# Ext_connections.net
KiCad netlist of a schematic drawn in Altium Designer
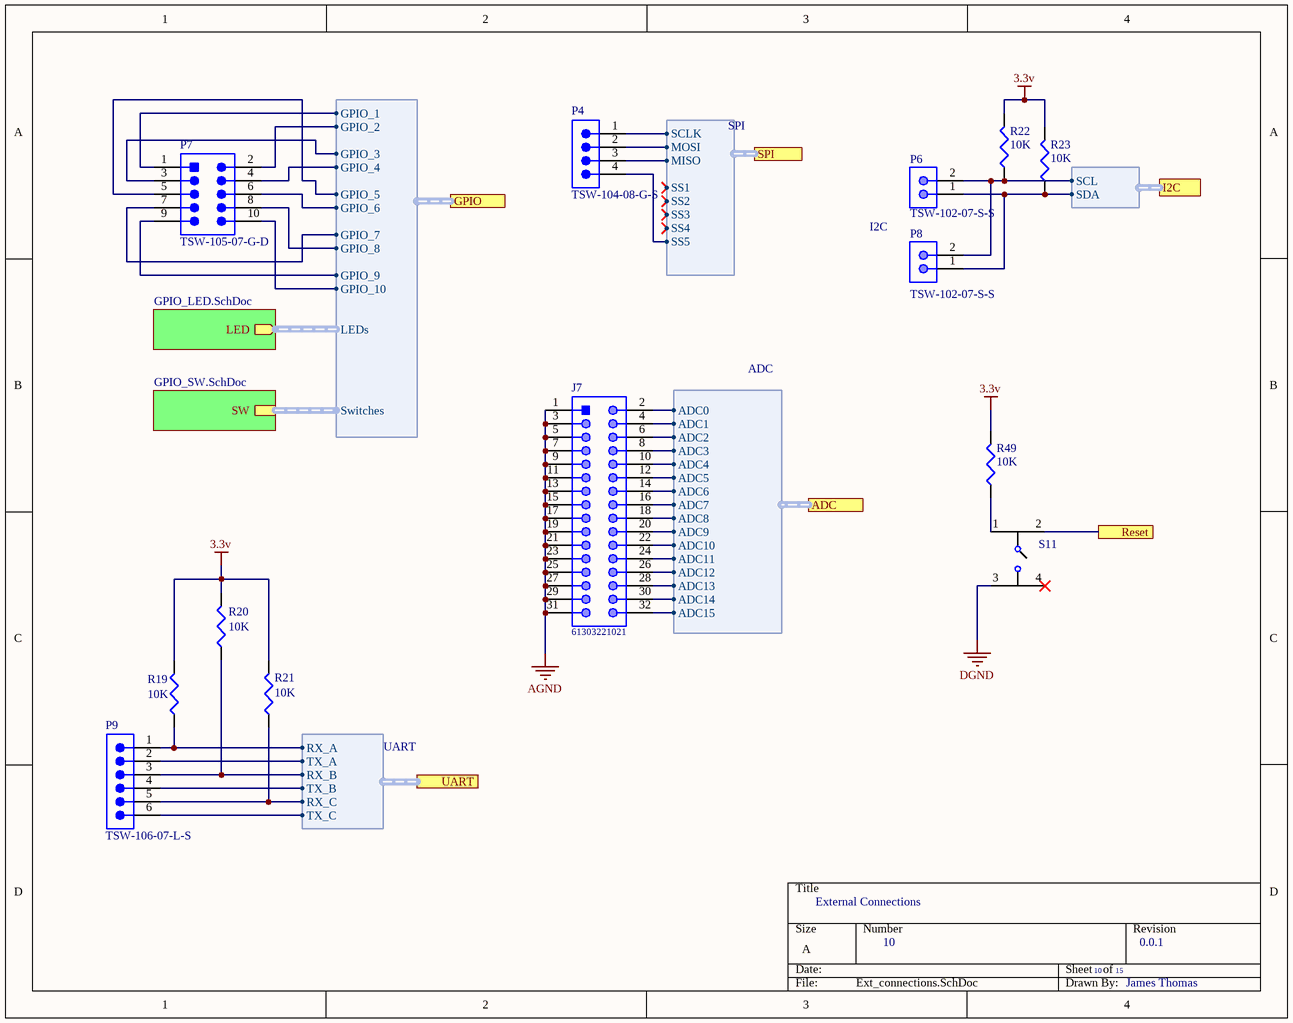
[diagram p0: Ext_connections.SchDoc]

(export (version "E")
  (design (tool "Eeschema 10.0.6"))
  (components
    (comp (ref "J7")
      (value "61303221021")
      (footprint "61303221021")
      (description "THT Angled Pin Header WR-PHD, Pitch 2.54 mm, Dual Row, 32 pins")
      (fields (field (name "MANUFACTURER") "Wurth Elektronik") (field (name "PUBLISHER") "WurthElektronik"))
      (libsource (lib "Altium Content Vault") (part "WE-CN-2P-M-R32"))
    )
    (comp (ref "P4")
      (value "TSW-104-08-G-S")
      (footprint "SMTC-TSW-104-08-X-S")
      (description "0.025\" SQ Post Header, Through-hole, Vertical, -55 to 125 degC, 2.54 mm Pitch, 4-Pin, Male, RoHS")
      (fields (field (name "MANUFACTURER") "Samtec"))
      (libsource (lib "Altium Content Vault") (part "SMTC-TSW-104-08-X-S"))
    )
    (comp (ref "P6")
      (value "TSW-102-07-S-S")
      (footprint "SMTC-TSW-102-07-S-S")
      (fields (field (name "MANUFACTURER") "Samtec"))
      (libsource (lib "Altium Content Vault") (part "CN-1P-M-R2"))
    )
    (comp (ref "P7")
      (value "TSW-105-07-G-D")
      (footprint "SMTC-TSW-105-07-G-D_V")
      (fields (field (name "MANUFACTURER") "Samtec-Inc."))
      (libsource (lib "Altium Content Vault") (part "CN-2P-M-R10"))
    )
    (comp (ref "P8")
      (value "TSW-102-07-S-S")
      (footprint "SMTC-TSW-102-07-S-S")
      (fields (field (name "MANUFACTURER") "Samtec"))
      (libsource (lib "Altium Content Vault") (part "CN-1P-M-R2"))
    )
    (comp (ref "P9")
      (value "TSW-106-07-L-S")
      (footprint "SMTC-TSW-106-07-X-S")
      (description "0.025\" SQ Post Header, Through-hole, Vertical, -55 to 125 degC, 2.54 mm Pitch, 6-Pin, Male, RoHS")
      (fields (field (name "MANUFACTURER") "Samtec"))
      (libsource (lib "Altium Content Vault") (part "SMTC-TSW-106-X-X-S-X"))
    )
    (comp (ref "R19")
      (value "10K")
      (footprint "J1-0603")
      (description "Resistor")
      (fields (field (name "Comment") "Res3") (field (name "PUBLISHER") "Altium Limited"))
      (libsource (lib "Miscellaneous Devices") (part "Res3"))
    )
    (comp (ref "R20")
      (value "10K")
      (footprint "J1-0603")
      (description "Resistor")
      (fields (field (name "Comment") "Res3") (field (name "PUBLISHER") "Altium Limited"))
      (libsource (lib "Miscellaneous Devices") (part "Res3"))
    )
    (comp (ref "R21")
      (value "10K")
      (footprint "J1-0603")
      (description "Resistor")
      (fields (field (name "Comment") "Res3") (field (name "PUBLISHER") "Altium Limited"))
      (libsource (lib "Miscellaneous Devices") (part "Res3"))
    )
    (comp (ref "R22")
      (value "10K")
      (footprint "J1-0603")
      (description "Resistor")
      (fields (field (name "Comment") "Res3") (field (name "PUBLISHER") "Altium Limited"))
      (libsource (lib "Miscellaneous Devices") (part "Res3"))
    )
    (comp (ref "R23")
      (value "10K")
      (footprint "J1-0603")
      (description "Resistor")
      (fields (field (name "Comment") "Res3") (field (name "PUBLISHER") "Altium Limited"))
      (libsource (lib "Miscellaneous Devices") (part "Res3"))
    )
    (comp (ref "R49")
      (value "10K")
      (footprint "J1-0603")
      (description "Resistor")
      (fields (field (name "Comment") "Res3") (field (name "PUBLISHER") "Altium Limited"))
      (libsource (lib "Miscellaneous Devices") (part "Res3"))
    )
    (comp (ref "S11")
      (value "430181038816")
      (footprint "*430181038816")
      (description "Tactile Switch SPST-NO Top Actuated Surface Mount")
      (fields (field (name "MF") "Wurth Electronics"))
      (libsource (lib "Components") (part "430181038816"))
    )
  )
  (nets
    (net (code "6") (name "/ADC0") (class "Default")
      (node (ref "J7") (pin "2") (pinfunction "2_2") (pintype "passive"))
    )
    (net (code "7") (name "/ADC1") (class "Default")
      (node (ref "J7") (pin "4") (pinfunction "4_4") (pintype "passive"))
    )
    (net (code "8") (name "/ADC2") (class "Default")
      (node (ref "J7") (pin "6") (pinfunction "6_6") (pintype "passive"))
    )
    (net (code "9") (name "/ADC3") (class "Default")
      (node (ref "J7") (pin "8") (pinfunction "8_8") (pintype "passive"))
    )
    (net (code "10") (name "/ADC4") (class "Default")
      (node (ref "J7") (pin "10") (pinfunction "10_10") (pintype "passive"))
    )
    (net (code "11") (name "/ADC5") (class "Default")
      (node (ref "J7") (pin "12") (pinfunction "12_12") (pintype "passive"))
    )
    (net (code "12") (name "/ADC6") (class "Default")
      (node (ref "J7") (pin "14") (pinfunction "14_14") (pintype "passive"))
    )
    (net (code "13") (name "/ADC7") (class "Default")
      (node (ref "J7") (pin "16") (pinfunction "16_16") (pintype "passive"))
    )
    (net (code "14") (name "/ADC8") (class "Default")
      (node (ref "J7") (pin "18") (pinfunction "18_18") (pintype "passive"))
    )
    (net (code "15") (name "/ADC9") (class "Default")
      (node (ref "J7") (pin "20") (pinfunction "20_20") (pintype "passive"))
    )
    (net (code "16") (name "/ADC10") (class "Default")
      (node (ref "J7") (pin "22") (pinfunction "22_22") (pintype "passive"))
    )
    (net (code "17") (name "/ADC11") (class "Default")
      (node (ref "J7") (pin "24") (pinfunction "24_24") (pintype "passive"))
    )
    (net (code "18") (name "/ADC12") (class "Default")
      (node (ref "J7") (pin "26") (pinfunction "26_26") (pintype "passive"))
    )
    (net (code "19") (name "/ADC13") (class "Default")
      (node (ref "J7") (pin "28") (pinfunction "28_28") (pintype "passive"))
    )
    (net (code "20") (name "/ADC14") (class "Default")
      (node (ref "J7") (pin "30") (pinfunction "30_30") (pintype "passive"))
    )
    (net (code "21") (name "/ADC15") (class "Default")
      (node (ref "J7") (pin "32") (pinfunction "32_32") (pintype "passive"))
    )
    (net (code "22") (name "/GPIO_1") (class "Default")
      (node (ref "P7") (pin "1") (pinfunction "1_1") (pintype "passive"))
    )
    (net (code "23") (name "/GPIO_2") (class "Default")
      (node (ref "P7") (pin "2") (pinfunction "2_2") (pintype "passive"))
    )
    (net (code "24") (name "/GPIO_3") (class "Default")
      (node (ref "P7") (pin "3") (pinfunction "3_3") (pintype "passive"))
    )
    (net (code "25") (name "/GPIO_4") (class "Default")
      (node (ref "P7") (pin "4") (pinfunction "4_4") (pintype "passive"))
    )
    (net (code "26") (name "/GPIO_5") (class "Default")
      (node (ref "P7") (pin "5") (pinfunction "5_5") (pintype "passive"))
    )
    (net (code "27") (name "/GPIO_6") (class "Default")
      (node (ref "P7") (pin "6") (pinfunction "6_6") (pintype "passive"))
    )
    (net (code "28") (name "/GPIO_7") (class "Default")
      (node (ref "P7") (pin "7") (pinfunction "7_7") (pintype "passive"))
    )
    (net (code "29") (name "/GPIO_8") (class "Default")
      (node (ref "P7") (pin "8") (pinfunction "8_8") (pintype "passive"))
    )
    (net (code "30") (name "/GPIO_9") (class "Default")
      (node (ref "P7") (pin "9") (pinfunction "9_9") (pintype "passive"))
    )
    (net (code "31") (name "/GPIO_10") (class "Default")
      (node (ref "P7") (pin "10") (pinfunction "10_10") (pintype "passive"))
    )
    (net (code "33") (name "/MISO") (class "Default")
      (node (ref "P4") (pin "3") (pinfunction "3_3") (pintype "passive"))
    )
    (net (code "34") (name "/MOSI") (class "Default")
      (node (ref "P4") (pin "2") (pinfunction "2_2") (pintype "passive"))
    )
    (net (code "35") (name "/RX_A") (class "Default")
      (node (ref "P9") (pin "1") (pinfunction "1_1") (pintype "passive"))
      (node (ref "R19") (pin "1") (pinfunction "1_1") (pintype "passive"))
    )
    (net (code "36") (name "/RX_B") (class "Default")
      (node (ref "P9") (pin "3") (pinfunction "3_3") (pintype "passive"))
      (node (ref "R20") (pin "1") (pinfunction "1_1") (pintype "passive"))
    )
    (net (code "37") (name "/RX_C") (class "Default")
      (node (ref "P9") (pin "5") (pinfunction "5_5") (pintype "passive"))
      (node (ref "R21") (pin "1") (pinfunction "1_1") (pintype "passive"))
    )
    (net (code "38") (name "/Reset") (class "Default")
      (node (ref "S11") (pin "2") (pinfunction "3_2") (pintype "passive"))
    )
    (net (code "39") (name "/SCL") (class "Default")
      (node (ref "P6") (pin "2") (pinfunction "2_2") (pintype "passive"))
      (node (ref "P8") (pin "2") (pinfunction "2_2") (pintype "passive"))
      (node (ref "R22") (pin "1") (pinfunction "1_1") (pintype "passive"))
    )
    (net (code "40") (name "/SCLK") (class "Default")
      (node (ref "P4") (pin "1") (pinfunction "1_1") (pintype "passive"))
    )
    (net (code "41") (name "/SDA") (class "Default")
      (node (ref "P6") (pin "1") (pinfunction "1_1") (pintype "passive"))
      (node (ref "P8") (pin "1") (pinfunction "1_1") (pintype "passive"))
      (node (ref "R23") (pin "1") (pinfunction "1_1") (pintype "passive"))
    )
    (net (code "42") (name "/SS5") (class "Default")
      (node (ref "P4") (pin "4") (pinfunction "4_4") (pintype "passive"))
    )
    (net (code "44") (name "/TX_A") (class "Default")
      (node (ref "P9") (pin "2") (pinfunction "2_2") (pintype "passive"))
    )
    (net (code "45") (name "/TX_B") (class "Default")
      (node (ref "P9") (pin "4") (pinfunction "4_4") (pintype "passive"))
    )
    (net (code "46") (name "/TX_C") (class "Default")
      (node (ref "P9") (pin "6") (pinfunction "6_6") (pintype "passive"))
    )
    (net (code "52") (name "3.3v") (class "Default")
      (node (ref "R19") (pin "2") (pinfunction "2_2") (pintype "passive"))
      (node (ref "R20") (pin "2") (pinfunction "2_2") (pintype "passive"))
      (node (ref "R21") (pin "2") (pinfunction "2_2") (pintype "passive"))
      (node (ref "R22") (pin "2") (pinfunction "2_2") (pintype "passive"))
      (node (ref "R23") (pin "2") (pinfunction "2_2") (pintype "passive"))
      (node (ref "R49") (pin "2") (pinfunction "2_2") (pintype "passive"))
    )
    (net (code "53") (name "AGND") (class "Default")
      (node (ref "J7") (pin "1") (pinfunction "1_1") (pintype "passive"))
      (node (ref "J7") (pin "11") (pinfunction "11_11") (pintype "passive"))
      (node (ref "J7") (pin "13") (pinfunction "13_13") (pintype "passive"))
      (node (ref "J7") (pin "15") (pinfunction "15_15") (pintype "passive"))
      (node (ref "J7") (pin "17") (pinfunction "17_17") (pintype "passive"))
      (node (ref "J7") (pin "19") (pinfunction "19_19") (pintype "passive"))
      (node (ref "J7") (pin "21") (pinfunction "21_21") (pintype "passive"))
      (node (ref "J7") (pin "23") (pinfunction "23_23") (pintype "passive"))
      (node (ref "J7") (pin "25") (pinfunction "25_25") (pintype "passive"))
      (node (ref "J7") (pin "27") (pinfunction "27_27") (pintype "passive"))
      (node (ref "J7") (pin "29") (pinfunction "29_29") (pintype "passive"))
      (node (ref "J7") (pin "3") (pinfunction "3_3") (pintype "passive"))
      (node (ref "J7") (pin "31") (pinfunction "31_31") (pintype "passive"))
      (node (ref "J7") (pin "5") (pinfunction "5_5") (pintype "passive"))
      (node (ref "J7") (pin "7") (pinfunction "7_7") (pintype "passive"))
      (node (ref "J7") (pin "9") (pinfunction "9_9") (pintype "passive"))
    )
    (net (code "54") (name "DGND") (class "Default")
      (node (ref "S11") (pin "3") (pinfunction "2_3") (pintype "passive"))
    )
    (net (code "55") (name "Net-(R49-Pad1)") (class "Default")
      (node (ref "R49") (pin "1") (pinfunction "1_1") (pintype "passive"))
      (node (ref "S11") (pin "1") (pinfunction "1_1") (pintype "passive"))
    )
    (net (code "56") (name "unconnected-(S11-Pad4)") (class "Default")
      (node (ref "S11") (pin "4") (pinfunction "4_4") (pintype "passive+no_connect"))
    )
  )
)
